# power_core.net
KiCad netlist of a schematic drawn in Altium Designer
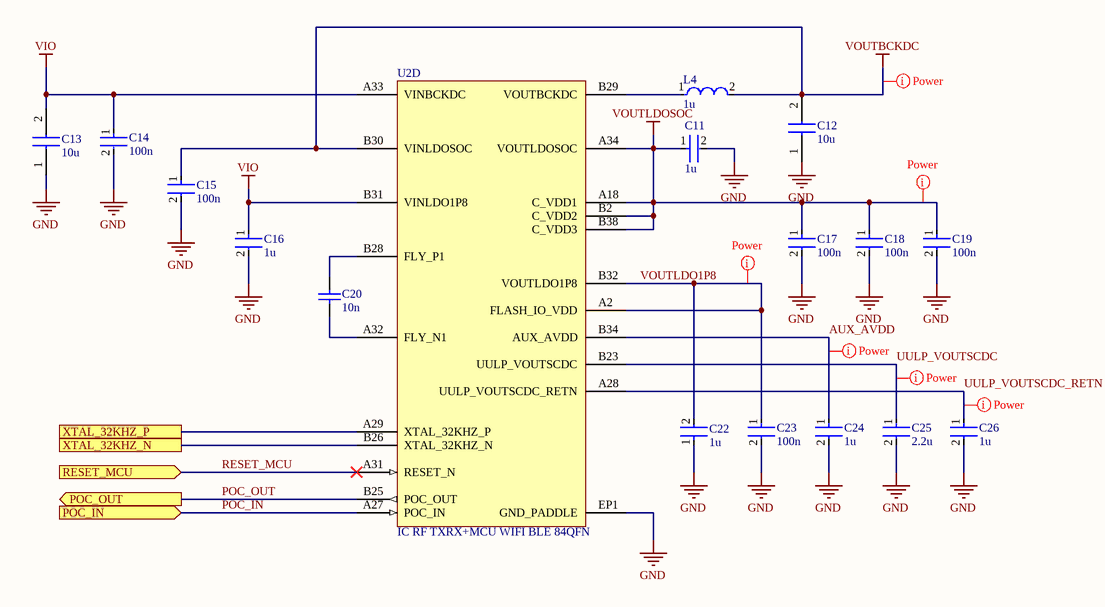
[diagram p0: power_core.SchDoc]

(export (version "E")
  (design (tool "Eeschema 10.0.6"))
  (components
    (comp (ref "C11")
      (value "1u")
      (footprint "FP-GRM155-0_05-MFG")
      (description "Chip Multilayer Ceramic Capacitors for General Purpose, 0402, 1.0uF, X6S, 22%, 10%, 16V")
      (fields (field (name "TOLERANCE") "10%"))
      (libsource (lib "Altium Content Vault") (part "02cd4be3c70576c341d710602a673aa"))
    )
    (comp (ref "C12")
      (value "10u")
      (footprint "SamacSys:CAPC1608X100N")
      (description "Cap Cer 10UF 10V X7R 0603")
      (fields (field (name "MANUFACTURER_PART_NUMBER") "GMC10X7R106K10NT"))
      (libsource (lib "*") (part "GMC10X7R106K10NT"))
    )
    (comp (ref "C13")
      (value "10u")
      (footprint "SamacSys:CAPC1608X100N")
      (description "Cap Cer 10UF 10V X7R 0603")
      (fields (field (name "MANUFACTURER_PART_NUMBER") "GMC10X7R106K10NT"))
      (libsource (lib "*") (part "GMC10X7R106K10NT"))
    )
    (comp (ref "C14")
      (value "100n")
      (footprint "FP-GRT155-0_05-MFG")
      (description "Multi-Layer Ceramic Capacitor 100nF 50V X7R ±10% 0402 Paper T/R")
      (libsource (lib "Altium Content Vault") (part "02cd4be3c70576c341d710602a673aa"))
    )
    (comp (ref "C15")
      (value "100n")
      (footprint "FP-GRT155-0_05-MFG")
      (description "Multi-Layer Ceramic Capacitor 100nF 50V X7R ±10% 0402 Paper T/R")
      (libsource (lib "Altium Content Vault") (part "02cd4be3c70576c341d710602a673aa"))
    )
    (comp (ref "C16")
      (value "1u")
      (footprint "FP-GRM155-0_05-MFG")
      (description "Chip Multilayer Ceramic Capacitors for General Purpose, 0402, 1.0uF, X6S, 22%, 10%, 16V")
      (fields (field (name "TOLERANCE") "10%"))
      (libsource (lib "Altium Content Vault") (part "02cd4be3c70576c341d710602a673aa"))
    )
    (comp (ref "C17")
      (value "100n")
      (footprint "FP-GRT155-0_05-MFG")
      (description "Multi-Layer Ceramic Capacitor 100nF 50V X7R ±10% 0402 Paper T/R")
      (libsource (lib "Altium Content Vault") (part "02cd4be3c70576c341d710602a673aa"))
    )
    (comp (ref "C18")
      (value "100n")
      (footprint "FP-GRT155-0_05-MFG")
      (description "Multi-Layer Ceramic Capacitor 100nF 50V X7R ±10% 0402 Paper T/R")
      (libsource (lib "Altium Content Vault") (part "02cd4be3c70576c341d710602a673aa"))
    )
    (comp (ref "C19")
      (value "100n")
      (footprint "FP-GRT155-0_05-MFG")
      (description "Multi-Layer Ceramic Capacitor 100nF 50V X7R ±10% 0402 Paper T/R")
      (libsource (lib "Altium Content Vault") (part "02cd4be3c70576c341d710602a673aa"))
    )
    (comp (ref "C20")
      (value "10n")
      (footprint "CAPC1005X55X25LL05T10")
      (fields (field (name "MANUFACTURER") "Murata") (field (name "PART NUMBER") "GRM155R71E103KA01D"))
      (libsource (lib "Altium Content Vault") (part "CAP"))
    )
    (comp (ref "C22")
      (value "1u")
      (footprint "FP-GRM155-0_05-MFG")
      (description "Chip Multilayer Ceramic Capacitors for General Purpose, 0402, 1.0uF, X6S, 22%, 10%, 16V")
      (fields (field (name "TOLERANCE") "10%"))
      (libsource (lib "Altium Content Vault") (part "02cd4be3c70576c341d710602a673aa"))
    )
    (comp (ref "C23")
      (value "100n")
      (footprint "FP-GRT155-0_05-MFG")
      (description "Multi-Layer Ceramic Capacitor 100nF 50V X7R ±10% 0402 Paper T/R")
      (libsource (lib "Altium Content Vault") (part "02cd4be3c70576c341d710602a673aa"))
    )
    (comp (ref "C24")
      (value "1u")
      (footprint "FP-GRM155-0_05-MFG")
      (description "Chip Multilayer Ceramic Capacitors for General Purpose, 0402, 1.0uF, X6S, 22%, 10%, 16V")
      (fields (field (name "TOLERANCE") "10%"))
      (libsource (lib "Altium Content Vault") (part "02cd4be3c70576c341d710602a673aa"))
    )
    (comp (ref "C25")
      (value "2.2u")
      (footprint "FP-GRM155-0_2-IPC_C")
      (description "Chip Multilayer Ceramic Capacitors for General Purpose, 0402, 2.2uF, X7S, 22%, 10%, 10V")
      (fields (field (name "TOLERANCE") "10%"))
      (libsource (lib "Altium Content Vault") (part "b4654b650e69147ec39a6b967a45e02"))
    )
    (comp (ref "C26")
      (value "1u")
      (footprint "FP-GRM155-0_05-MFG")
      (description "Chip Multilayer Ceramic Capacitors for General Purpose, 0402, 1.0uF, X6S, 22%, 10%, 16V")
      (fields (field (name "TOLERANCE") "10%"))
      (libsource (lib "Altium Content Vault") (part "02cd4be3c70576c341d710602a673aa"))
    )
    (comp (ref "L4")
      (value "1u")
      (footprint "FP-DFE201210U-IPC_C")
      (description "FIXED IND 1.0UH 2.0A 95MOHM")
      (libsource (lib "Altium Content Vault") (part "725321dda6339637d4d059423bc1c3c"))
    )
    (comp (ref "U2")
      (value "IC RF TXRX+MCU WIFI BLE 84QFN")
      (footprint "wius:SIWG917M110LGTBA")
      (libsource (lib "wius") (part "SIWG917"))
    )
  )
  (nets
    (net (code "1") (name "/AUX_AVDD") (class "Default")
      (node (ref "C24") (pin "1") (pinfunction "1_1") (pintype "passive"))
      (node (ref "U2") (pin "B34") (pinfunction "AUX_AVDD_B34") (pintype "passive"))
    )
    (net (code "2") (name "/POC_IN") (class "Default")
      (node (ref "U2") (pin "A27") (pinfunction "POC_IN_A27") (pintype "input"))
    )
    (net (code "3") (name "/POC_OUT") (class "Default")
      (node (ref "U2") (pin "B25") (pinfunction "POC_OUT_B25") (pintype "output"))
    )
    (net (code "4") (name "/RESET_MCU") (class "Default")
      (node (ref "U2") (pin "A31") (pinfunction "RESET_N_A31") (pintype "input+no_connect"))
    )
    (net (code "5") (name "/UULP_VOUTSCDC") (class "Default")
      (node (ref "C25") (pin "1") (pinfunction "1_1") (pintype "passive"))
      (node (ref "U2") (pin "B23") (pinfunction "UULP_VOUTSCDC_B23") (pintype "passive"))
    )
    (net (code "6") (name "/UULP_VOUTSCDC_RETN") (class "Default")
      (node (ref "C26") (pin "1") (pinfunction "1_1") (pintype "passive"))
      (node (ref "U2") (pin "A28") (pinfunction "UULP_VOUTSCDC_RETN_A28") (pintype "passive"))
    )
    (net (code "7") (name "/VOUTLDO1P8") (class "Default")
      (node (ref "C22") (pin "2") (pinfunction "2_2") (pintype "passive"))
      (node (ref "C23") (pin "1") (pinfunction "1_1") (pintype "passive"))
      (node (ref "U2") (pin "A2") (pinfunction "FLASH_IO_VDD_A2") (pintype "power_in"))
      (node (ref "U2") (pin "B32") (pinfunction "VOUTLDO1P8_B32") (pintype "power_in"))
    )
    (net (code "8") (name "/XTAL_32KHZ_N") (class "Default")
      (node (ref "U2") (pin "B26") (pinfunction "XTAL_32KHZ_N_B26") (pintype "passive"))
    )
    (net (code "9") (name "/XTAL_32KHZ_P") (class "Default")
      (node (ref "U2") (pin "A29") (pinfunction "XTAL_32KHZ_P_A29") (pintype "passive"))
    )
    (net (code "10") (name "GND") (class "Default")
      (node (ref "C11") (pin "2") (pinfunction "2_2") (pintype "passive"))
      (node (ref "C12") (pin "1") (pinfunction "1_1") (pintype "passive"))
      (node (ref "C13") (pin "1") (pinfunction "1_1") (pintype "passive"))
      (node (ref "C14") (pin "2") (pinfunction "2_2") (pintype "passive"))
      (node (ref "C15") (pin "2") (pinfunction "2_2") (pintype "passive"))
      (node (ref "C16") (pin "2") (pinfunction "2_2") (pintype "passive"))
      (node (ref "C17") (pin "2") (pinfunction "2_2") (pintype "passive"))
      (node (ref "C18") (pin "2") (pinfunction "2_2") (pintype "passive"))
      (node (ref "C19") (pin "2") (pinfunction "2_2") (pintype "passive"))
      (node (ref "C22") (pin "1") (pinfunction "1_1") (pintype "passive"))
      (node (ref "C23") (pin "2") (pinfunction "2_2") (pintype "passive"))
      (node (ref "C24") (pin "2") (pinfunction "2_2") (pintype "passive"))
      (node (ref "C25") (pin "2") (pinfunction "2_2") (pintype "passive"))
      (node (ref "C26") (pin "2") (pinfunction "2_2") (pintype "passive"))
      (node (ref "U2") (pin "EP1") (pinfunction "GND_PADDLE_EP1") (pintype "power_in"))
    )
    (net (code "11") (name "Net-(U2D-FLY_N1)") (class "Default")
      (node (ref "C20") (pin "2") (pinfunction "2_2") (pintype "passive"))
      (node (ref "U2") (pin "A32") (pinfunction "FLY_N1_A32") (pintype "passive"))
    )
    (net (code "12") (name "Net-(U2D-FLY_P1)") (class "Default")
      (node (ref "C20") (pin "1") (pinfunction "1_1") (pintype "passive"))
      (node (ref "U2") (pin "B28") (pinfunction "FLY_P1_B28") (pintype "passive"))
    )
    (net (code "13") (name "Net-(U2D-VOUTBCKDC)") (class "Default")
      (node (ref "L4") (pin "1") (pinfunction "1_1") (pintype "passive"))
      (node (ref "U2") (pin "B29") (pinfunction "VOUTBCKDC_B29") (pintype "power_in"))
    )
    (net (code "14") (name "VIO") (class "Default")
      (node (ref "C13") (pin "2") (pinfunction "2_2") (pintype "passive"))
      (node (ref "C14") (pin "1") (pinfunction "1_1") (pintype "passive"))
      (node (ref "C16") (pin "1") (pinfunction "1_1") (pintype "passive"))
      (node (ref "U2") (pin "A33") (pinfunction "VINBCKDC_A33") (pintype "power_in"))
      (node (ref "U2") (pin "B31") (pinfunction "VINLDO1P8_B31") (pintype "power_in"))
    )
    (net (code "15") (name "VOUTBCKDC") (class "Default")
      (node (ref "C12") (pin "2") (pinfunction "2_2") (pintype "passive"))
      (node (ref "C15") (pin "1") (pinfunction "1_1") (pintype "passive"))
      (node (ref "L4") (pin "2") (pinfunction "2_2") (pintype "passive"))
      (node (ref "U2") (pin "B30") (pinfunction "VINLDOSOC_B30") (pintype "power_in"))
    )
    (net (code "16") (name "VOUTLDOSOC") (class "Default")
      (node (ref "C11") (pin "1") (pinfunction "1_1") (pintype "passive"))
      (node (ref "C17") (pin "1") (pinfunction "1_1") (pintype "passive"))
      (node (ref "C18") (pin "1") (pinfunction "1_1") (pintype "passive"))
      (node (ref "C19") (pin "1") (pinfunction "1_1") (pintype "passive"))
      (node (ref "U2") (pin "A18") (pinfunction "C_VDD1_A18") (pintype "power_in"))
      (node (ref "U2") (pin "A34") (pinfunction "VOUTLDOSOC_A34") (pintype "power_in"))
      (node (ref "U2") (pin "B2") (pinfunction "C_VDD2_B2") (pintype "power_in"))
      (node (ref "U2") (pin "B38") (pinfunction "C_VDD3_B38") (pintype "power_in"))
    )
  )
)
